# Power.net
KiCad netlist of a schematic drawn in Altium Designer
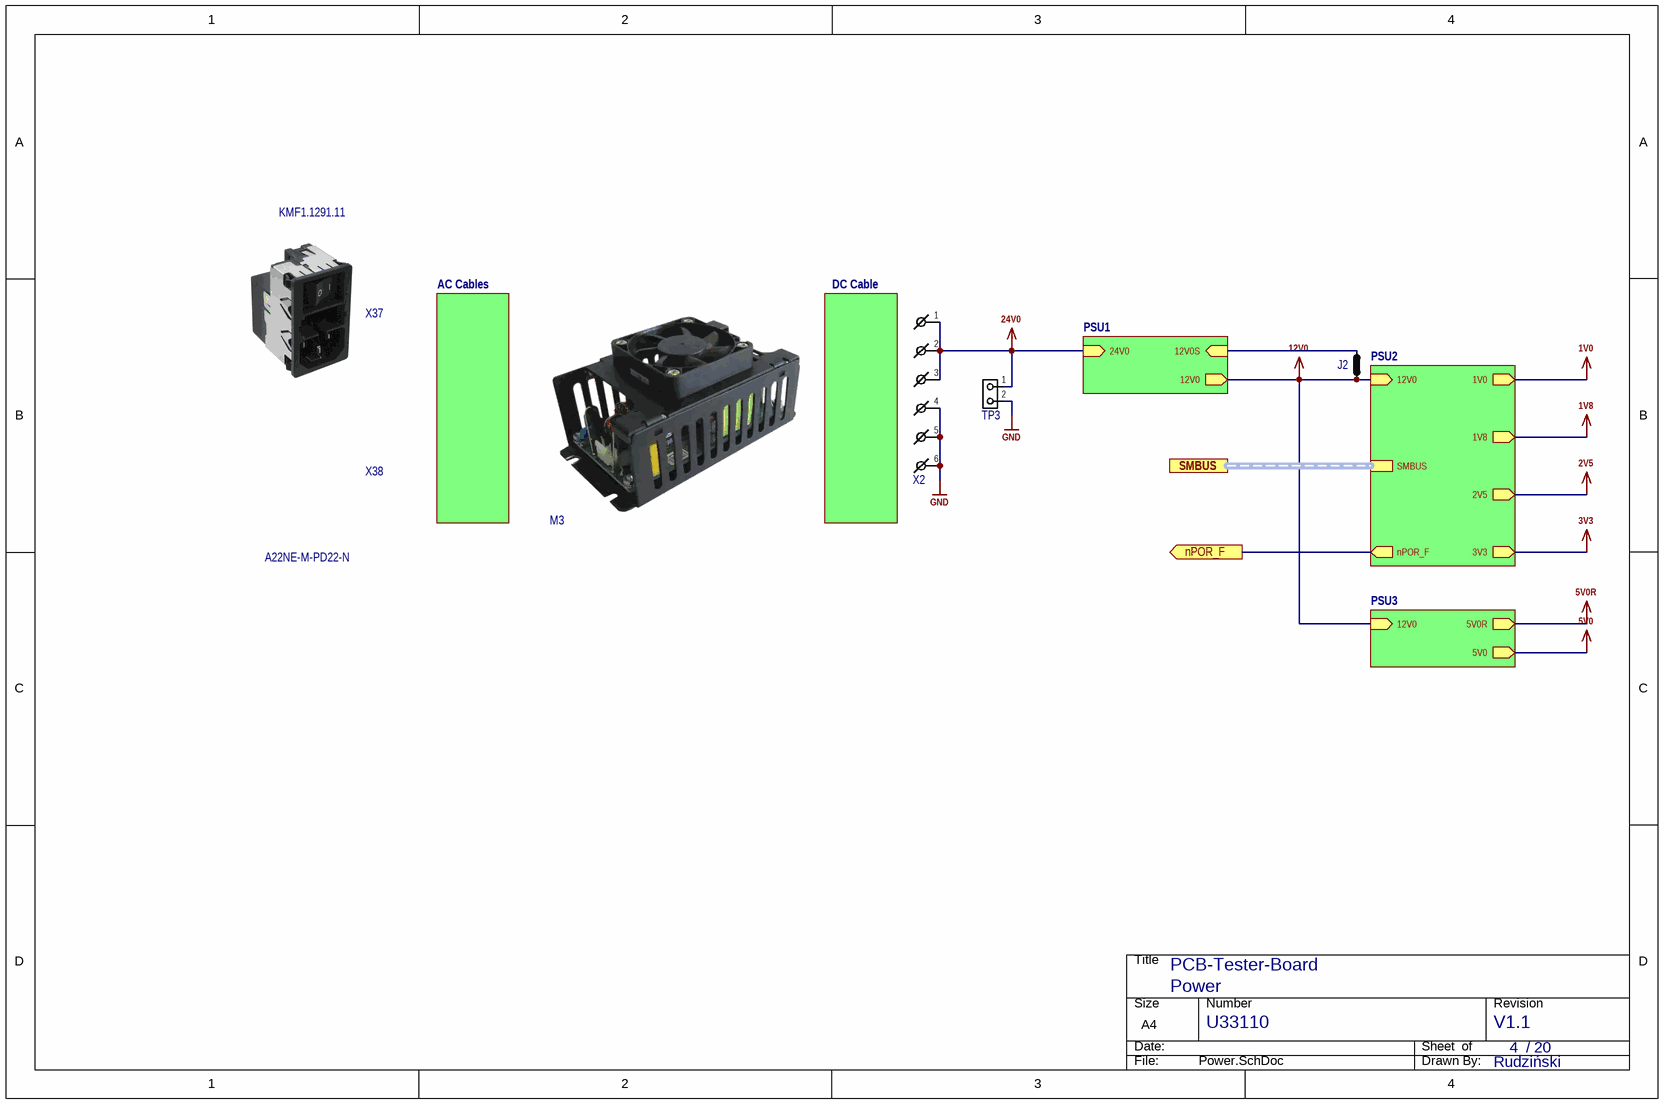
[diagram p0: Power.SchDoc]

(export (version "E")
  (design (tool "Eeschema 10.0.6"))
  (components
    (comp (ref "J2")
      (value "J")
      (footprint "NT0201")
      (description "Net Tie")
      (fields (field (name "13. CREATED DATE/NAME") "AUG2018/Hören"))
      (libsource (lib "chickenfood") (part "NT"))
    )
    (comp (ref "M3")
      (value "M")
      (description "AC DC CONVERTER 85~264VAC --> 24VDC (6A)")
      (fields
        (field (name "02. DISTRIBUTOR PART NUMBER") "285-3030-ND")
        (field (name "07. MANUFACTURER  PART NUMBER") "CUS150M24/F")
        (field (name "13. CREATED DATE/NAME") "AUG 2018 / Hören")
      )
      (libsource (lib "PCB-Tester-Board-V1") (part "CUS150M-24/F"))
    )
    (comp (ref "TP3")
      (value "TP")
      (footprint "DualTestpoint 100mils")
      (description "Dual testpoint, pitch 2.54mm")
      (fields
        (field (name "02. DISTRIBUTOR PART NUMBER") "HMTSW-103-07-G-S-240")
        (field (name "13. CREATED DATE/NAME") "AUG2018/Hören")
      )
      (libsource (lib "PCB-Tester-Board-V1") (part "DualTestpoint 100mils"))
    )
    (comp (ref "X2")
      (value "X")
      (footprint "B6PS-VH")
      (description "CONN HEADER R/A 6POS 3.96MM")
      (fields
        (field (name "02. DISTRIBUTOR PART NUMBER") "455-1652-ND")
        (field (name "07. MANUFACTURER  PART NUMBER") "B6PS-VH(LF)(SN)")
        (field (name "13. CREATED DATE/NAME") "AUG 2018 / Hören")
      )
      (libsource (lib "Connectors") (part "B6PS-VH"))
    )
    (comp (ref "X37")
      (value "X")
      (description "PWR ENT MOD RCPT IEC320-C14 PNL")
      (fields
        (field (name "02. DISTRIBUTOR PART NUMBER") "486-2292-ND")
        (field (name "07. MANUFACTURER  PART NUMBER") "KMF1.1291.11")
        (field (name "13. CREATED DATE/NAME") "AUG 2018 / Hören")
      )
      (libsource (lib "PCB-Tester-Board") (part "KMF1-1291-11"))
    )
    (comp (ref "X38")
      (value "X")
      (description "E-STOP 40MM 2NO/2NC TURN RESET")
      (fields
        (field (name "02. DISTRIBUTOR PART NUMBER") "236-A22NE-M-PD22-N-ND")
        (field (name "07. MANUFACTURER  PART NUMBER") "A22NE-M-PD22-N")
        (field (name "13. CREATED DATE/NAME") "AUG 2018 / Hören")
      )
      (libsource (lib "PCB-Tester-Board") (part "A22NE-M-PD22-N"))
    )
  )
  (nets
    (net (code "2") (name "/12V0S") (class "Default")
      (node (ref "J2") (pin "2") (pinfunction "2_2") (pintype "passive"))
    )
    (net (code "11") (name "12V0") (class "Default")
      (node (ref "J2") (pin "1") (pinfunction "1_1") (pintype "passive"))
    )
    (net (code "12") (name "24V0") (class "Default")
      (node (ref "TP3") (pin "1") (pinfunction "1_1") (pintype "passive"))
      (node (ref "X2") (pin "1") (pinfunction "1_1") (pintype "passive"))
      (node (ref "X2") (pin "2") (pinfunction "2_2") (pintype "passive"))
      (node (ref "X2") (pin "3") (pinfunction "3_3") (pintype "passive"))
    )
    (net (code "13") (name "GND") (class "Default")
      (node (ref "TP3") (pin "2") (pinfunction "2_2") (pintype "passive"))
      (node (ref "X2") (pin "4") (pinfunction "4_4") (pintype "passive"))
      (node (ref "X2") (pin "5") (pinfunction "5_5") (pintype "passive"))
      (node (ref "X2") (pin "6") (pinfunction "6_6") (pintype "passive"))
    )
  )
)
